# Flash.net
KiCad netlist of a schematic drawn in Altium Designer
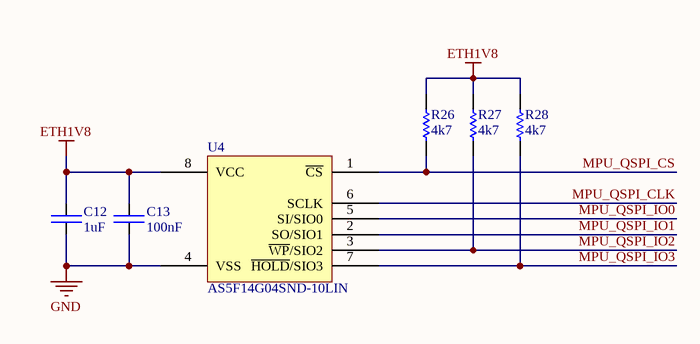
[diagram p0: Flash.SchDoc]

(export (version "E")
  (design (tool "Eeschema 10.0.6"))
  (components
    (comp (ref "C12")
      (value "1uF")
      (footprint "CAP-0805")
      (description "Capacitor chip unpolarized. 0805")
      (libsource (lib "Master") (part "CAP-0805"))
    )
    (comp (ref "C13")
      (value "100nF")
      (footprint "CAP-0603")
      (description "Capacitor chip unpolarized. 0603")
      (libsource (lib "Master") (part "CAP-0603"))
    )
    (comp (ref "R26")
      (value "4k7")
      (footprint "RES-0603")
      (description "Resistor chip. 0603")
      (libsource (lib "Master") (part "RES-0603"))
    )
    (comp (ref "R27")
      (value "4k7")
      (footprint "RES-0603")
      (description "Resistor chip. 0603")
      (libsource (lib "Master") (part "RES-0603"))
    )
    (comp (ref "R28")
      (value "4k7")
      (footprint "RES-0603")
      (description "Resistor chip. 0603")
      (libsource (lib "Master") (part "RES-0603"))
    )
    (comp (ref "U4")
      (value "AS5F14G04SND-10LIN")
      (footprint "AS5F34G04SNDA-08LIN")
      (description "FLASH SPI/QUAD 4GBIT")
      (libsource (lib "Master") (part "AS5F34G04SNDA-08LIN"))
    )
  )
  (nets
    (net (code "1") (name "/MPU_QSPI_CLK") (class "Default")
      (node (ref "U4") (pin "6") (pinfunction "SCLK_6") (pintype "passive"))
    )
    (net (code "2") (name "/MPU_QSPI_CS") (class "Default")
      (node (ref "R26") (pin "1") (pintype "passive"))
      (node (ref "U4") (pin "1") (pinfunction "~{CS}_1") (pintype "passive"))
    )
    (net (code "3") (name "/MPU_QSPI_IO0") (class "Default")
      (node (ref "U4") (pin "5") (pinfunction "SI/SIO0_5") (pintype "passive"))
    )
    (net (code "4") (name "/MPU_QSPI_IO1") (class "Default")
      (node (ref "U4") (pin "2") (pinfunction "SO/SIO1_2") (pintype "passive"))
    )
    (net (code "5") (name "/MPU_QSPI_IO2") (class "Default")
      (node (ref "R27") (pin "1") (pintype "passive"))
      (node (ref "U4") (pin "3") (pinfunction "~{WP}/SIO2_3") (pintype "passive"))
    )
    (net (code "6") (name "/MPU_QSPI_IO3") (class "Default")
      (node (ref "R28") (pin "1") (pintype "passive"))
      (node (ref "U4") (pin "7") (pinfunction "~{HOLD}/SIO3_7") (pintype "passive"))
    )
    (net (code "7") (name "ETH1V8") (class "Default")
      (node (ref "C12") (pin "2") (pintype "passive"))
      (node (ref "C13") (pin "2") (pintype "passive"))
      (node (ref "R26") (pin "2") (pintype "passive"))
      (node (ref "R27") (pin "2") (pintype "passive"))
      (node (ref "R28") (pin "2") (pintype "passive"))
      (node (ref "U4") (pin "8") (pinfunction "VCC_8") (pintype "passive"))
    )
    (net (code "8") (name "GND") (class "Default")
      (node (ref "C12") (pin "1") (pintype "passive"))
      (node (ref "C13") (pin "1") (pintype "passive"))
      (node (ref "U4") (pin "4") (pinfunction "VSS_4") (pintype "passive"))
    )
  )
)
